# Transceiver.net
KiCad netlist of a schematic drawn in Altium Designer
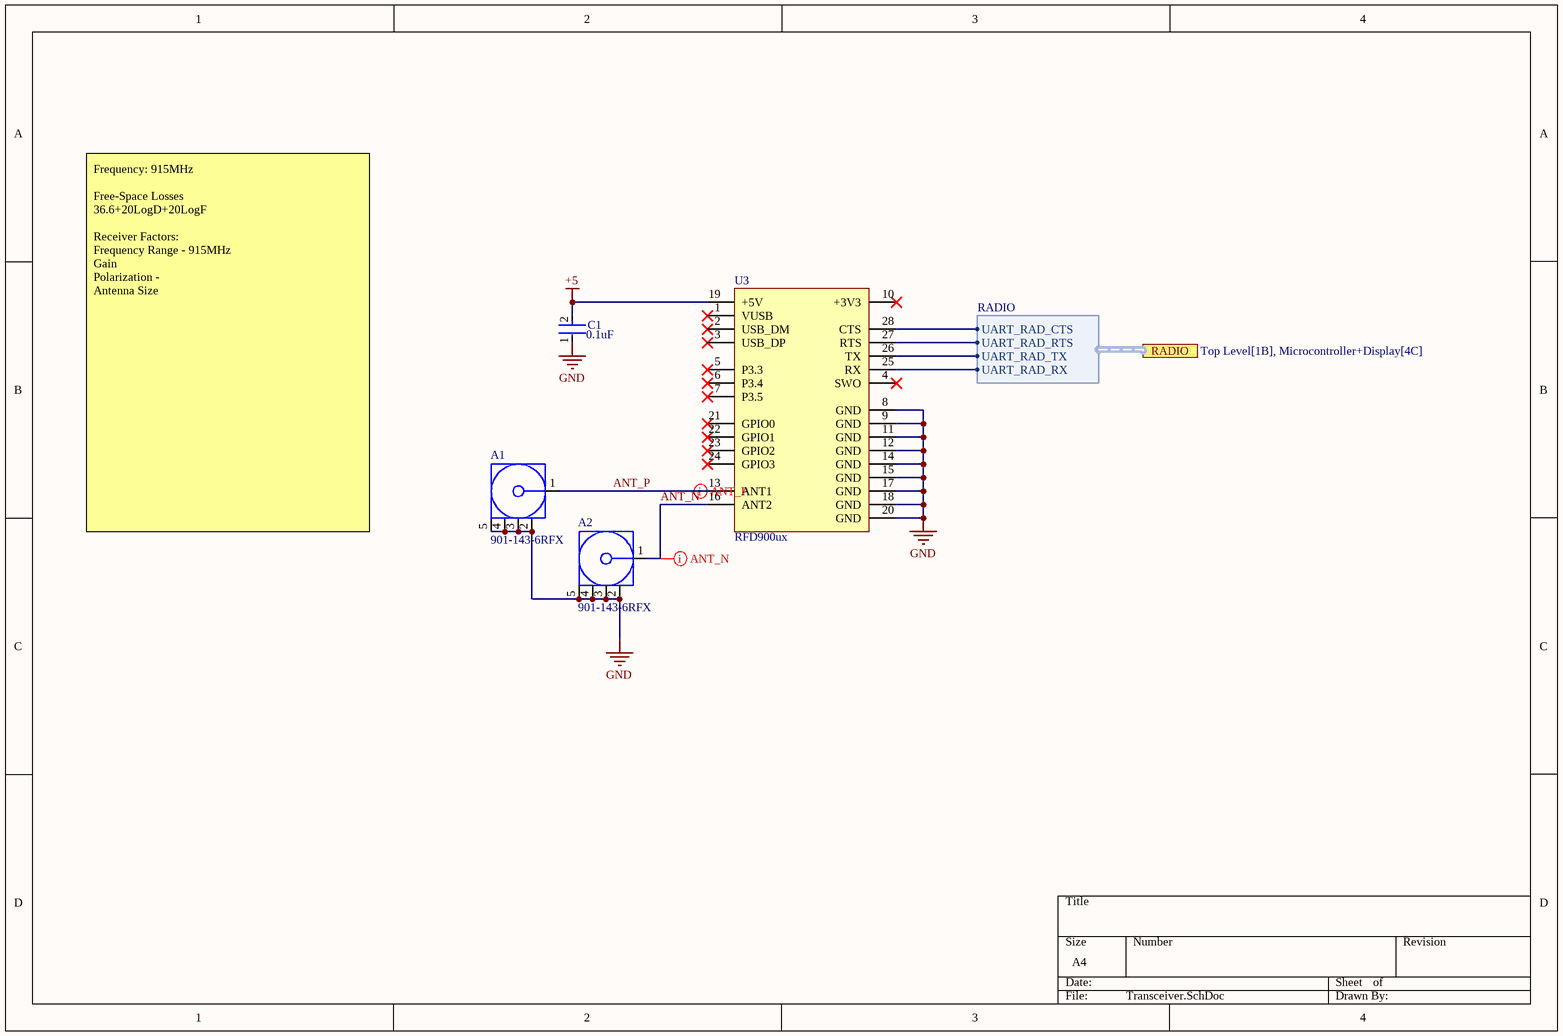
[diagram p0: Transceiver.SchDoc]

(export (version "E")
  (design (tool "Eeschema 10.0.6"))
  (components
    (comp (ref "A1")
      (value "901-143-6RFX")
      (footprint "903-143-6RFX")
      (libsource (lib "Receiver_Library") (part "901-143-6RFX"))
    )
    (comp (ref "A2")
      (value "901-143-6RFX")
      (footprint "903-143-6RFX")
      (libsource (lib "Receiver_Library") (part "901-143-6RFX"))
    )
    (comp (ref "C1")
      (value "C1608X5R1A106K080AC")
      (footprint "FP-C1608-080-0_1-MFG")
      (description "Multilayer Ceramic Capacitors 10μF ±10% 10V X5R SMD 0603")
      (fields
        (field (name "VOLTAGE") "10V")
        (field (name "TOLERANCE") "10%")
        (field (name "CAPACITANCE") "0.1uF")
      )
      (libsource (lib "Altium Content Vault") (part "236180d848d6139a670b325ea6854c9"))
    )
    (comp (ref "U3")
      (value "RFD900ux")
      (footprint "RFD900UX")
      (libsource (lib "Receiver_Library") (part "RFD900ux"))
    )
  )
  (nets
    (net (code "2") (name "+5") (class "Default")
      (node (ref "C1") (pin "2") (pinfunction "2_2") (pintype "passive"))
      (node (ref "U3") (pin "19") (pinfunction "+5V_19") (pintype "passive"))
    )
    (net (code "3") (name "/ANT_N") (class "Default")
      (node (ref "A2") (pin "1") (pinfunction "1_1") (pintype "passive"))
      (node (ref "U3") (pin "16") (pinfunction "ANT2_16") (pintype "passive"))
    )
    (net (code "4") (name "/ANT_P") (class "Default")
      (node (ref "A1") (pin "1") (pinfunction "1_1") (pintype "passive"))
      (node (ref "U3") (pin "13") (pinfunction "ANT1_13") (pintype "passive"))
    )
    (net (code "5") (name "/UART_RAD_CTS") (class "Default")
      (node (ref "U3") (pin "28") (pinfunction "CTS_28") (pintype "passive"))
    )
    (net (code "6") (name "/UART_RAD_RTS") (class "Default")
      (node (ref "U3") (pin "27") (pinfunction "RTS_27") (pintype "passive"))
    )
    (net (code "7") (name "/UART_RAD_RX") (class "Default")
      (node (ref "U3") (pin "25") (pinfunction "RX_25") (pintype "passive"))
    )
    (net (code "8") (name "/UART_RAD_TX") (class "Default")
      (node (ref "U3") (pin "26") (pinfunction "TX_26") (pintype "passive"))
    )
    (net (code "10") (name "GND") (class "Default")
      (node (ref "A1") (pin "2") (pinfunction "2_2") (pintype "passive"))
      (node (ref "A1") (pin "3") (pinfunction "3_3") (pintype "passive"))
      (node (ref "A1") (pin "4") (pinfunction "4_4") (pintype "passive"))
      (node (ref "A1") (pin "5") (pinfunction "5_5") (pintype "passive"))
      (node (ref "A2") (pin "2") (pinfunction "2_2") (pintype "passive"))
      (node (ref "A2") (pin "3") (pinfunction "3_3") (pintype "passive"))
      (node (ref "A2") (pin "4") (pinfunction "4_4") (pintype "passive"))
      (node (ref "A2") (pin "5") (pinfunction "5_5") (pintype "passive"))
      (node (ref "C1") (pin "1") (pinfunction "1_1") (pintype "passive"))
      (node (ref "U3") (pin "11") (pinfunction "GND_11") (pintype "passive"))
      (node (ref "U3") (pin "12") (pinfunction "GND_12") (pintype "passive"))
      (node (ref "U3") (pin "14") (pinfunction "GND_14") (pintype "passive"))
      (node (ref "U3") (pin "15") (pinfunction "GND_15") (pintype "passive"))
      (node (ref "U3") (pin "17") (pinfunction "GND_17") (pintype "passive"))
      (node (ref "U3") (pin "18") (pinfunction "GND_18") (pintype "passive"))
      (node (ref "U3") (pin "20") (pinfunction "GND_20") (pintype "passive"))
      (node (ref "U3") (pin "8") (pinfunction "GND_8") (pintype "passive"))
      (node (ref "U3") (pin "9") (pinfunction "GND_9") (pintype "passive"))
    )
    (net (code "11") (name "unconnected-(U3-+3V3-Pad10)") (class "Default")
      (node (ref "U3") (pin "10") (pinfunction "+3V3_10") (pintype "passive+no_connect"))
    )
    (net (code "12") (name "unconnected-(U3-GPIO0-Pad21)") (class "Default")
      (node (ref "U3") (pin "21") (pinfunction "GPIO0_21") (pintype "passive+no_connect"))
    )
    (net (code "13") (name "unconnected-(U3-GPIO1-Pad22)") (class "Default")
      (node (ref "U3") (pin "22") (pinfunction "GPIO1_22") (pintype "passive+no_connect"))
    )
    (net (code "14") (name "unconnected-(U3-GPIO2-Pad23)") (class "Default")
      (node (ref "U3") (pin "23") (pinfunction "GPIO2_23") (pintype "passive+no_connect"))
    )
    (net (code "15") (name "unconnected-(U3-GPIO3-Pad24)") (class "Default")
      (node (ref "U3") (pin "24") (pinfunction "GPIO3_24") (pintype "passive+no_connect"))
    )
    (net (code "16") (name "unconnected-(U3-P3.3-Pad5)") (class "Default")
      (node (ref "U3") (pin "5") (pinfunction "P3.3_5") (pintype "passive+no_connect"))
    )
    (net (code "17") (name "unconnected-(U3-P3.4-Pad6)") (class "Default")
      (node (ref "U3") (pin "6") (pinfunction "P3.4_6") (pintype "passive+no_connect"))
    )
    (net (code "18") (name "unconnected-(U3-P3.5-Pad7)") (class "Default")
      (node (ref "U3") (pin "7") (pinfunction "P3.5_7") (pintype "passive+no_connect"))
    )
    (net (code "19") (name "unconnected-(U3-SWO-Pad4)") (class "Default")
      (node (ref "U3") (pin "4") (pinfunction "SWO_4") (pintype "passive+no_connect"))
    )
    (net (code "20") (name "unconnected-(U3-USB_DM-Pad2)") (class "Default")
      (node (ref "U3") (pin "2") (pinfunction "USB_DM_2") (pintype "passive+no_connect"))
    )
    (net (code "21") (name "unconnected-(U3-USB_DP-Pad3)") (class "Default")
      (node (ref "U3") (pin "3") (pinfunction "USB_DP_3") (pintype "passive+no_connect"))
    )
    (net (code "22") (name "unconnected-(U3-VUSB-Pad1)") (class "Default")
      (node (ref "U3") (pin "1") (pinfunction "VUSB_1") (pintype "passive+no_connect"))
    )
  )
)
